# Power_Supply.net
KiCad netlist of a schematic drawn in Altium Designer
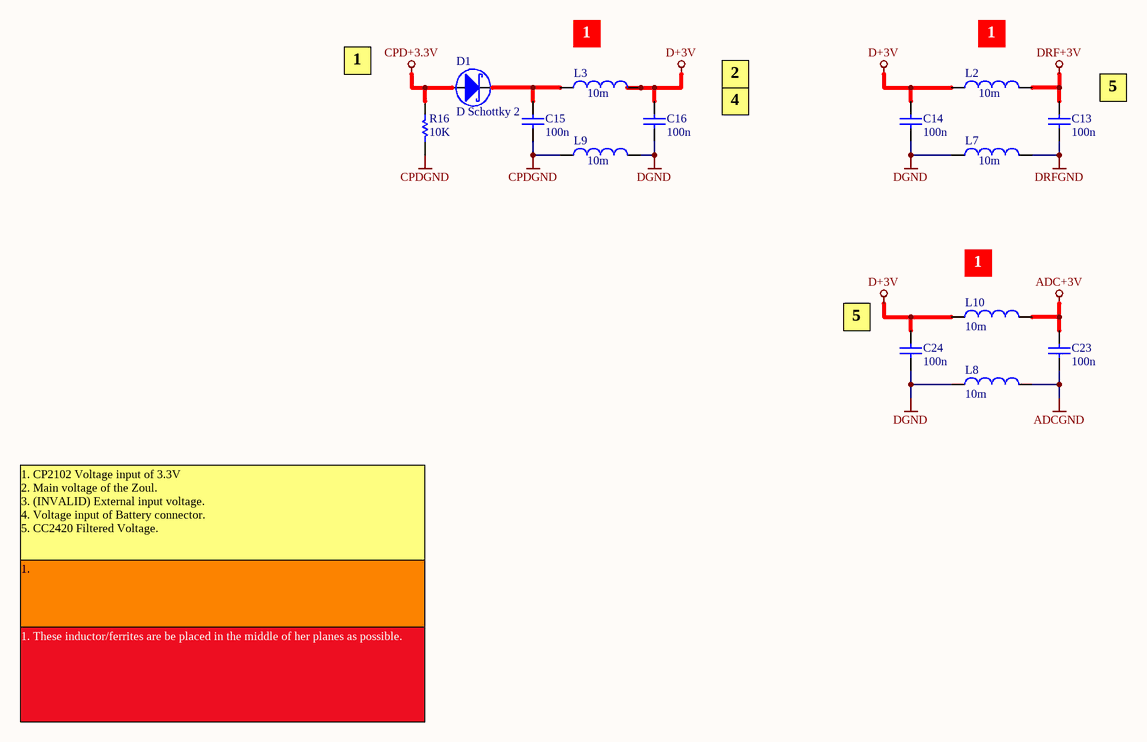
[diagram p0: Power Supply.SchDoc]

(export (version "E")
  (design (tool "Eeschema 10.0.6"))
  (components
    (comp (ref "C13")
      (value "100n")
      (footprint "CC-0402-AL")
      (description "Capacitor (Semiconductor SIM Model)")
      (fields (field (name "Comment") "Cap Semi"))
      (libsource (lib "Z1_Project") (part "Cap Semi"))
    )
    (comp (ref "C14")
      (value "100n")
      (footprint "CC-0402-AL")
      (description "Capacitor (Semiconductor SIM Model)")
      (fields (field (name "Comment") "Cap Semi"))
      (libsource (lib "Z1_Project") (part "Cap Semi"))
    )
    (comp (ref "C15")
      (value "100n")
      (footprint "CC-0402-AL")
      (description "Capacitor (Semiconductor SIM Model)")
      (fields (field (name "Comment") "Cap Semi"))
      (libsource (lib "Z1_Project") (part "Cap Semi"))
    )
    (comp (ref "C16")
      (value "100n")
      (footprint "CC-0402-AL")
      (description "Capacitor (Semiconductor SIM Model)")
      (fields (field (name "Comment") "Cap Semi"))
      (libsource (lib "Z1_Project") (part "Cap Semi"))
    )
    (comp (ref "C23")
      (value "100n")
      (footprint "CC-0402-AL")
      (description "Capacitor (Semiconductor SIM Model)")
      (fields (field (name "Comment") "Cap Semi"))
      (libsource (lib "Z1_Project") (part "Cap Semi"))
    )
    (comp (ref "C24")
      (value "100n")
      (footprint "CC-0402-AL")
      (description "Capacitor (Semiconductor SIM Model)")
      (fields (field (name "Comment") "Cap Semi"))
      (libsource (lib "Z1_Project") (part "Cap Semi"))
    )
    (comp (ref "D1")
      (value "D Schottky 2")
      (footprint "STPS140A")
      (description "Schotkky Diode 1N5820")
      (libsource (lib "Z1_Project") (part "D Schottky 2"))
    )
    (comp (ref "L2")
      (value "10m")
      (footprint "CR-0402-AL")
      (description "Inductor")
      (libsource (lib "Z1_Project") (part "Inductor"))
    )
    (comp (ref "L3")
      (value "10m")
      (footprint "CR-0402-AL")
      (description "Inductor")
      (libsource (lib "Z1_Project") (part "Inductor"))
    )
    (comp (ref "L7")
      (value "10m")
      (footprint "CR-0402-AL")
      (description "Inductor")
      (libsource (lib "Z1_Project") (part "Inductor"))
    )
    (comp (ref "L8")
      (value "10m")
      (footprint "CR-0402-AL")
      (description "Inductor")
      (libsource (lib "") (part "Inductor_1"))
    )
    (comp (ref "L9")
      (value "10m")
      (footprint "CR-0402-AL")
      (description "Inductor")
      (libsource (lib "Z1_Project") (part "Inductor"))
    )
    (comp (ref "L10")
      (value "10m")
      (footprint "CR-0402-AL")
      (description "Inductor")
      (libsource (lib "") (part "Inductor_1"))
    )
    (comp (ref "R16")
      (value "10K")
      (footprint "CR-0402-AL")
      (description "Semiconductor Resistor")
      (fields (field (name "MANUFACTURER") "Generic Components") (field (name "Comment") "Res Semi"))
      (libsource (lib "Z1_Project") (part "Res Semi"))
    )
  )
  (nets
    (net (code "1") (name "ADC+3V") (class "Default")
      (node (ref "C23") (pin "2") (pinfunction "2_2") (pintype "passive"))
      (node (ref "L10") (pin "1") (pinfunction "1_1") (pintype "passive"))
    )
    (net (code "2") (name "ADCGND") (class "Default")
      (node (ref "C23") (pin "1") (pinfunction "1_1") (pintype "passive"))
      (node (ref "L8") (pin "1") (pinfunction "1_1") (pintype "passive"))
    )
    (net (code "3") (name "CPD+3.3V") (class "Default")
      (node (ref "D1") (pin "1") (pinfunction "A_1") (pintype "passive"))
      (node (ref "R16") (pin "1") (pinfunction "1_1") (pintype "passive"))
    )
    (net (code "4") (name "CPDGND") (class "Default")
      (node (ref "C15") (pin "2") (pinfunction "2_2") (pintype "passive"))
      (node (ref "L9") (pin "1") (pinfunction "1_1") (pintype "passive"))
      (node (ref "R16") (pin "2") (pinfunction "2_2") (pintype "passive"))
    )
    (net (code "5") (name "D+3V") (class "Default")
      (node (ref "C14") (pin "2") (pinfunction "2_2") (pintype "passive"))
      (node (ref "C16") (pin "1") (pinfunction "1_1") (pintype "passive"))
      (node (ref "C24") (pin "1") (pinfunction "1_1") (pintype "passive"))
      (node (ref "L10") (pin "2") (pinfunction "2_2") (pintype "passive"))
      (node (ref "L2") (pin "1") (pinfunction "1_1") (pintype "passive"))
      (node (ref "L3") (pin "2") (pinfunction "2_2") (pintype "passive"))
    )
    (net (code "6") (name "DGND") (class "Default")
      (node (ref "C14") (pin "1") (pinfunction "1_1") (pintype "passive"))
      (node (ref "C16") (pin "2") (pinfunction "2_2") (pintype "passive"))
      (node (ref "C24") (pin "2") (pinfunction "2_2") (pintype "passive"))
      (node (ref "L7") (pin "1") (pinfunction "1_1") (pintype "passive"))
      (node (ref "L8") (pin "2") (pinfunction "2_2") (pintype "passive"))
      (node (ref "L9") (pin "2") (pinfunction "2_2") (pintype "passive"))
    )
    (net (code "7") (name "DRF+3V") (class "Default")
      (node (ref "C13") (pin "1") (pinfunction "1_1") (pintype "passive"))
      (node (ref "L2") (pin "2") (pinfunction "2_2") (pintype "passive"))
    )
    (net (code "8") (name "DRFGND") (class "Default")
      (node (ref "C13") (pin "2") (pinfunction "2_2") (pintype "passive"))
      (node (ref "L7") (pin "2") (pinfunction "2_2") (pintype "passive"))
    )
    (net (code "9") (name "Net-(D1-K)") (class "Default")
      (node (ref "C15") (pin "1") (pinfunction "1_1") (pintype "passive"))
      (node (ref "D1") (pin "2") (pinfunction "K_2") (pintype "passive"))
      (node (ref "L3") (pin "1") (pinfunction "1_1") (pintype "passive"))
    )
  )
)
